# Connector.net
KiCad netlist of a schematic drawn in Altium Designer
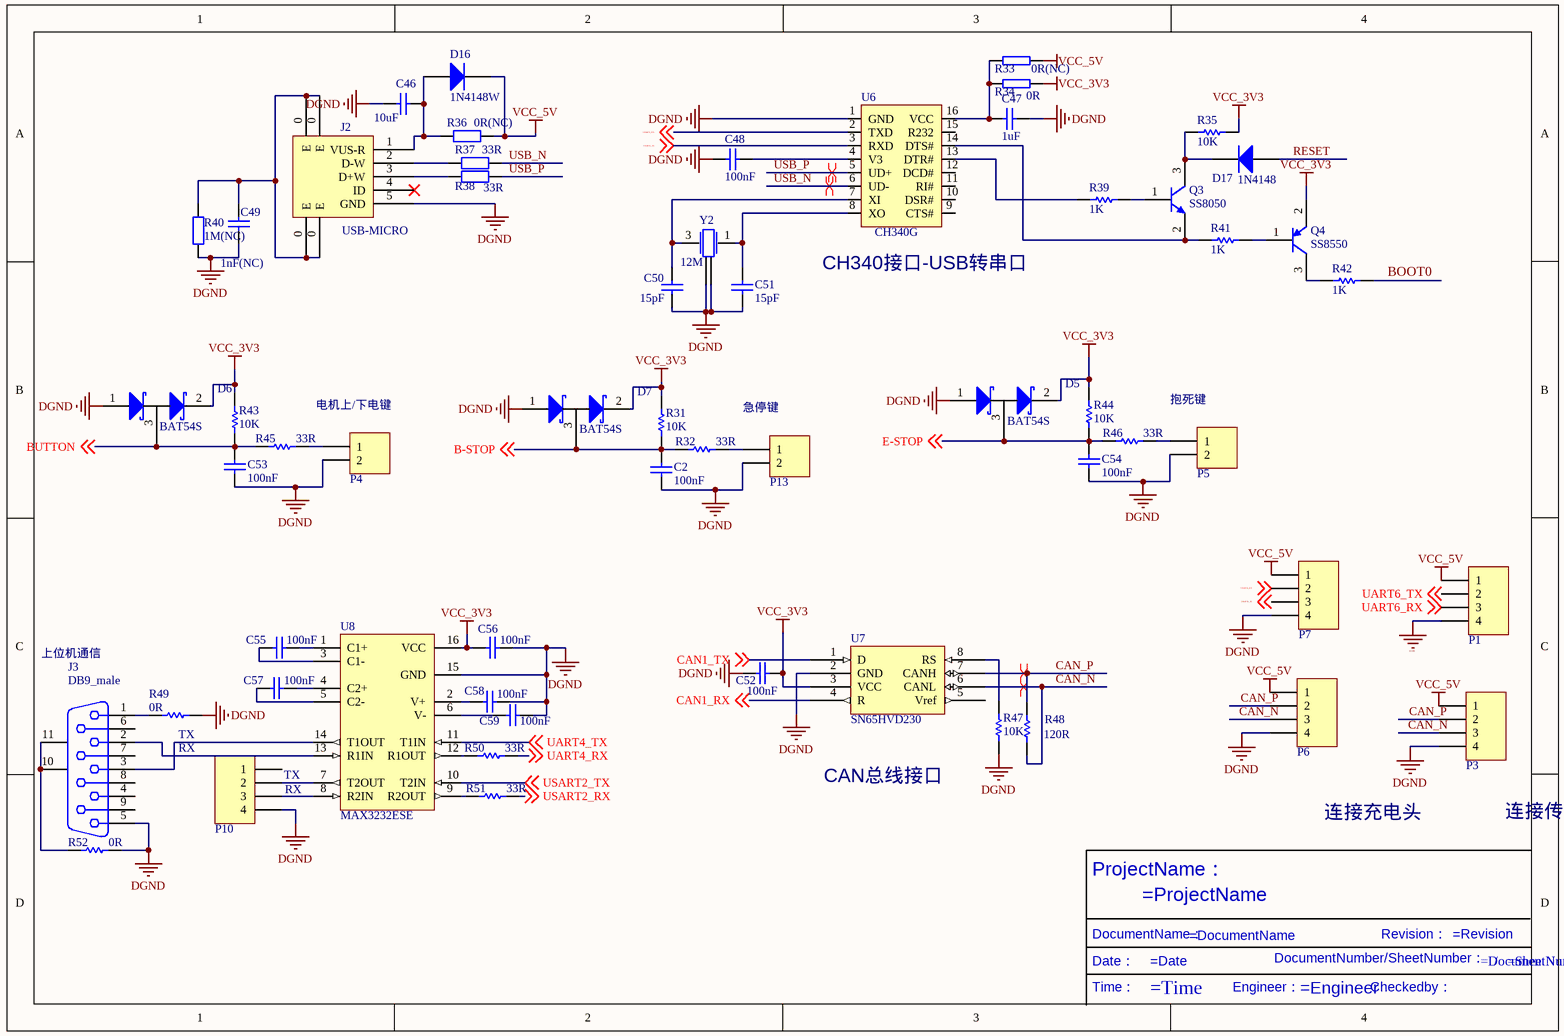
[diagram p0: Connector.SchDoc]

(export (version "E")
  (design (tool "Eeschema 10.0.6"))
  (components
    (comp (ref "C2")
      (value "100nF")
      (footprint "C-RAD-0805")
      (description "Capacitor")
      (fields (field (name "Comment") "100nF/±10%/50Vdc") (field (name "PUBLISHER") "Altium Limited"))
      (libsource (lib "boocax_schlib") (part "Cap"))
    )
    (comp (ref "C46")
      (value "10uF")
      (footprint "C-RAD-0805")
      (description "Capacitor")
      (fields (field (name "Comment") "10uF/±10%/50Vdc") (field (name "PUBLISHER") "Altium Limited"))
      (libsource (lib "boocax_schlib") (part "Cap"))
    )
    (comp (ref "C47")
      (value "1uF")
      (footprint "C-RAD-0805")
      (description "Capacitor")
      (fields (field (name "Comment") "1uF/±10%/50Vdc") (field (name "PUBLISHER") "Altium Limited"))
      (libsource (lib "boocax_schlib") (part "Cap"))
    )
    (comp (ref "C48")
      (value "100nF")
      (footprint "C-RAD-0805")
      (description "Capacitor")
      (fields (field (name "Comment") "100nF/±10%/50Vdc") (field (name "PUBLISHER") "Altium Limited"))
      (libsource (lib "boocax_schlib") (part "Cap"))
    )
    (comp (ref "C49")
      (value "1nF(NC)")
      (footprint "C-RAD-0805")
      (description "Capacitor")
      (fields (field (name "Comment") "Cap") (field (name "PUBLISHER") "Altium Limited"))
      (libsource (lib "boocax_schlib") (part "Cap"))
    )
    (comp (ref "C50")
      (value "15pF")
      (footprint "C-RAD-0805")
      (description "Capacitor")
      (fields (field (name "Comment") "15pF/±10%/50Vdc") (field (name "PUBLISHER") "Altium Limited"))
      (libsource (lib "boocax_schlib") (part "Cap"))
    )
    (comp (ref "C51")
      (value "15pF")
      (footprint "C-RAD-0805")
      (description "Capacitor")
      (fields (field (name "Comment") "15pF/±10%/50Vdc") (field (name "PUBLISHER") "Altium Limited"))
      (libsource (lib "boocax_schlib") (part "Cap"))
    )
    (comp (ref "C52")
      (value "100nF")
      (footprint "C-RAD-0805")
      (description "Capacitor")
      (fields (field (name "Comment") "100nF/±10%/50Vdc") (field (name "PUBLISHER") "Altium Limited"))
      (libsource (lib "boocax_schlib") (part "Cap"))
    )
    (comp (ref "C53")
      (value "100nF")
      (footprint "C-RAD-0805")
      (description "Capacitor")
      (fields (field (name "Comment") "100nF/±10%/50Vdc") (field (name "PUBLISHER") "Altium Limited"))
      (libsource (lib "boocax_schlib") (part "Cap"))
    )
    (comp (ref "C54")
      (value "100nF")
      (footprint "C-RAD-0805")
      (description "Capacitor")
      (fields (field (name "Comment") "100nF/±10%/50Vdc") (field (name "PUBLISHER") "Altium Limited"))
      (libsource (lib "boocax_schlib") (part "Cap"))
    )
    (comp (ref "C55")
      (value "100nF")
      (footprint "C-RAD-0805")
      (description "Capacitor")
      (fields (field (name "Comment") "100nF/±10%/50Vdc") (field (name "PUBLISHER") "Altium Limited"))
      (libsource (lib "boocax_schlib") (part "Cap"))
    )
    (comp (ref "C56")
      (value "100nF")
      (footprint "C-RAD-0805")
      (description "Capacitor")
      (fields (field (name "Comment") "100nF/±10%/50Vdc") (field (name "PUBLISHER") "Altium Limited"))
      (libsource (lib "boocax_schlib") (part "Cap"))
    )
    (comp (ref "C57")
      (value "100nF")
      (footprint "C-RAD-0805")
      (description "Capacitor")
      (fields (field (name "Comment") "100nF/±10%/50Vdc") (field (name "PUBLISHER") "Altium Limited"))
      (libsource (lib "boocax_schlib") (part "Cap"))
    )
    (comp (ref "C58")
      (value "100nF")
      (footprint "C-RAD-0805")
      (description "Capacitor")
      (fields (field (name "Comment") "100nF/±10%/50Vdc") (field (name "PUBLISHER") "Altium Limited"))
      (libsource (lib "boocax_schlib") (part "Cap"))
    )
    (comp (ref "C59")
      (value "100nF")
      (footprint "C-RAD-0805")
      (description "Capacitor")
      (fields (field (name "Comment") "100nF/±10%/50Vdc") (field (name "PUBLISHER") "Altium Limited"))
      (libsource (lib "boocax_schlib") (part "Cap"))
    )
    (comp (ref "D5")
      (value "BAT54S")
      (footprint "SOT-23")
      (description "双向肖特基二极管")
      (libsource (lib "Schlib1") (part "BAT54S"))
    )
    (comp (ref "D6")
      (value "BAT54S")
      (footprint "SOT-23")
      (description "双向肖特基二极管")
      (libsource (lib "Schlib1") (part "BAT54S"))
    )
    (comp (ref "D7")
      (value "BAT54S")
      (footprint "SOT-23")
      (description "双向肖特基二极管")
      (libsource (lib "Schlib1") (part "BAT54S"))
    )
    (comp (ref "D16")
      (value "1N4148W")
      (footprint "DIODE-1206")
      (description "二极管")
      (fields (field (name "PUBLISHER") "Altium Limited"))
      (libsource (lib "Sensor_V1.0.0") (part "Diode"))
    )
    (comp (ref "D17")
      (value "1N4148")
      (footprint "DIODE-1206")
      (description "二极管")
      (fields (field (name "Comment") "1N4148W") (field (name "PUBLISHER") "Altium Limited"))
      (libsource (lib "Sensor_V1.0.0") (part "Diode"))
    )
    (comp (ref "J2")
      (value "USB-MICRO")
      (footprint "USB-MICRO-1")
      (libsource (lib "boocax_schlib") (part "USB-MICRO"))
    )
    (comp (ref "J3")
      (value "DB9_male")
      (footprint "DB9-M")
      (description "串口")
      (fields (field (name "PUBLISHER") "Altium Limited"))
      (libsource (lib "founder") (part "D Connector 9"))
    )
    (comp (ref "P1")
      (value "Header 4")
      (footprint "SM04B-PBV")
      (description "接插件")
      (fields (field (name "PUBLISHER") "Altium Limited"))
      (libsource (lib "fszhang") (part "Header 4"))
    )
    (comp (ref "P3")
      (value "Header 4")
      (footprint "SM04B-PBV")
      (description "接插件")
      (fields (field (name "PUBLISHER") "Altium Limited"))
      (libsource (lib "fszhang") (part "Header 4"))
    )
    (comp (ref "P4")
      (value "Header 2")
      (footprint "MOLEX-2P")
      (description "接插件")
      (fields (field (name "PUBLISHER") "Altium Limited"))
      (libsource (lib "Fszhang") (part "Header 2"))
    )
    (comp (ref "P5")
      (value "Header 2")
      (footprint "MOLEX-2P")
      (description "接插件")
      (fields (field (name "PUBLISHER") "Altium Limited"))
      (libsource (lib "Fszhang") (part "Header 2"))
    )
    (comp (ref "P6")
      (value "Header 4")
      (footprint "SM04B-PBV")
      (description "接插件")
      (fields (field (name "PUBLISHER") "Altium Limited"))
      (libsource (lib "fszhang") (part "Header 4"))
    )
    (comp (ref "P7")
      (value "Header 4")
      (footprint "SM04B-PBV")
      (description "接插件")
      (fields (field (name "PUBLISHER") "Altium Limited"))
      (libsource (lib "fszhang") (part "Header 4"))
    )
    (comp (ref "P10")
      (value "Header 4")
      (footprint "SM04B-PBV")
      (description "接插件")
      (fields (field (name "PUBLISHER") "Altium Limited"))
      (libsource (lib "") (part "Header 4_1"))
    )
    (comp (ref "P13")
      (value "Header 2")
      (footprint "MOLEX-2P")
      (description "接插件")
      (fields (field (name "PUBLISHER") "Altium Limited"))
      (libsource (lib "Fszhang") (part "Header 2"))
    )
    (comp (ref "Q3")
      (value "SS8050")
      (footprint "SOT-23")
      (description "NPN贴片三极管")
      (fields (field (name "PUBLISHER") "Altium Limited"))
      (libsource (lib "Fszhang") (part "SS8050"))
    )
    (comp (ref "Q4")
      (value "SS8550")
      (footprint "SOT-23")
      (description "PNP贴片三极管")
      (fields (field (name "PUBLISHER") "Altium Limited"))
      (libsource (lib "Fszhang") (part "SS8550"))
    )
    (comp (ref "R31")
      (value "10K")
      (footprint "0805-1")
      (description "Resistor")
      (fields (field (name "Comment") "10K 5% 1/16W 0805") (field (name "PUBLISHER") "Altium Limited"))
      (libsource (lib "boocax_schlib") (part "Res1"))
    )
    (comp (ref "R32")
      (value "33R")
      (footprint "0805-1")
      (description "Resistor")
      (fields (field (name "Comment") "33R 5% 1/16W 0805") (field (name "PUBLISHER") "Altium Limited"))
      (libsource (lib "boocax_schlib") (part "Res1"))
    )
    (comp (ref "R33")
      (value "0R(NC)")
      (footprint "0805-1")
      (fields (field (name "Comment") "0R 5% 1/16W 0805(NC)"))
      (libsource (lib "luyjsch") (part "RES"))
    )
    (comp (ref "R34")
      (value "0R")
      (footprint "0805-1")
      (fields (field (name "Comment") "0R 5% 1/16W 0805"))
      (libsource (lib "luyjsch") (part "RES"))
    )
    (comp (ref "R35")
      (value "10K")
      (footprint "0805-1")
      (description "Resistor")
      (fields (field (name "Comment") "10K 5% 1/16W 0805") (field (name "PUBLISHER") "Altium Limited"))
      (libsource (lib "boocax_schlib") (part "Res1"))
    )
    (comp (ref "R36")
      (value "0R(NC)")
      (footprint "0805-1")
      (description "贴片电阻")
      (fields (field (name "Comment") "0R 5% 1/16W 0805(NC)") (field (name "PUBLISHER") "Altium Limited"))
      (libsource (lib "Compiled_Libraries") (part "Res1"))
    )
    (comp (ref "R37")
      (value "33R")
      (footprint "0805-1")
      (description "贴片电阻")
      (fields (field (name "Comment") "33R 5% 1/16W 0805") (field (name "PUBLISHER") "Altium Limited"))
      (libsource (lib "Compiled_Libraries") (part "Res1"))
    )
    (comp (ref "R38")
      (value "33R")
      (footprint "0805-1")
      (description "贴片电阻")
      (fields (field (name "Comment") "33R 5% 1/16W 0805") (field (name "PUBLISHER") "Altium Limited"))
      (libsource (lib "Compiled_Libraries") (part "Res1"))
    )
    (comp (ref "R39")
      (value "1K")
      (footprint "0805-1")
      (description "Resistor")
      (fields (field (name "Comment") "1K 5% 1/16W 0805") (field (name "PUBLISHER") "Altium Limited"))
      (libsource (lib "boocax_schlib") (part "Res1"))
    )
    (comp (ref "R40")
      (value "1M(NC)")
      (footprint "0805-1")
      (description "贴片电阻")
      (fields (field (name "Comment") "1M 5% 1/16W 0805(NC)") (field (name "PUBLISHER") "Altium Limited"))
      (libsource (lib "") (part "Res1_1"))
    )
    (comp (ref "R41")
      (value "1K")
      (footprint "0805-1")
      (description "Resistor")
      (fields (field (name "Comment") "1K 5% 1/16W 0805") (field (name "PUBLISHER") "Altium Limited"))
      (libsource (lib "boocax_schlib") (part "Res1"))
    )
    (comp (ref "R42")
      (value "1K")
      (footprint "0805-1")
      (description "Resistor")
      (fields (field (name "Comment") "1K 5% 1/16W 0805") (field (name "PUBLISHER") "Altium Limited"))
      (libsource (lib "boocax_schlib") (part "Res1"))
    )
    (comp (ref "R43")
      (value "10K")
      (footprint "0805-1")
      (description "Resistor")
      (fields (field (name "Comment") "10K 5% 1/16W 0805") (field (name "PUBLISHER") "Altium Limited"))
      (libsource (lib "boocax_schlib") (part "Res1"))
    )
    (comp (ref "R44")
      (value "10K")
      (footprint "0805-1")
      (description "Resistor")
      (fields (field (name "Comment") "10K 5% 1/16W 0805") (field (name "PUBLISHER") "Altium Limited"))
      (libsource (lib "boocax_schlib") (part "Res1"))
    )
    (comp (ref "R45")
      (value "33R")
      (footprint "0805-1")
      (description "Resistor")
      (fields (field (name "Comment") "33R 5% 1/16W 0805") (field (name "PUBLISHER") "Altium Limited"))
      (libsource (lib "boocax_schlib") (part "Res1"))
    )
    (comp (ref "R46")
      (value "33R")
      (footprint "0805-1")
      (description "Resistor")
      (fields (field (name "Comment") "33R 5% 1/16W 0805") (field (name "PUBLISHER") "Altium Limited"))
      (libsource (lib "boocax_schlib") (part "Res1"))
    )
    (comp (ref "R47")
      (value "10K")
      (footprint "0805-1")
      (description "Resistor")
      (fields (field (name "Comment") "10K 5% 1/16W 0805") (field (name "PUBLISHER") "Altium Limited"))
      (libsource (lib "boocax_schlib") (part "Res1"))
    )
    (comp (ref "R48")
      (value "120R")
      (footprint "0805-1")
      (description "Resistor")
      (fields (field (name "Comment") "120R 5% 1/16W 0805") (field (name "PUBLISHER") "Altium Limited"))
      (libsource (lib "boocax_schlib") (part "Res1"))
    )
    (comp (ref "R49")
      (value "0R")
      (footprint "0805-1")
      (description "Resistor")
      (fields (field (name "Comment") "0R 5% 1/16W 0805") (field (name "PUBLISHER") "Altium Limited"))
      (libsource (lib "boocax_schlib") (part "Res1"))
    )
    (comp (ref "R50")
      (value "33R")
      (footprint "0805-1")
      (description "Resistor")
      (fields (field (name "Comment") "33R 5% 1/16W 0805") (field (name "PUBLISHER") "Altium Limited"))
      (libsource (lib "boocax_schlib") (part "Res1"))
    )
    (comp (ref "R51")
      (value "33R")
      (footprint "0805-1")
      (description "Resistor")
      (fields (field (name "Comment") "33R 5% 1/16W 0805") (field (name "PUBLISHER") "Altium Limited"))
      (libsource (lib "boocax_schlib") (part "Res1"))
    )
    (comp (ref "R52")
      (value "0R")
      (footprint "0805-1")
      (description "Resistor")
      (fields (field (name "Comment") "0R 5% 1/16W 0805") (field (name "PUBLISHER") "Altium Limited"))
      (libsource (lib "boocax_schlib") (part "Res1"))
    )
    (comp (ref "U6")
      (value "CH340G")
      (footprint "SOP16")
      (description "串口转USB芯片")
      (libsource (lib "luyjsch") (part "CH340G"))
    )
    (comp (ref "U7")
      (value "SN65HVD230")
      (footprint "SO8-SN65HVD230")
      (libsource (lib "boocax_schlib") (part "SN65HVD230D"))
    )
    (comp (ref "U8")
      (value "MAX3232ESE")
      (footprint "SOP16")
      (description "+5V Powered, Multi-Channel RS-232 Driver/Receiver")
      (fields (field (name "PUBLISHER") "Altium Limited"))
      (libsource (lib "BABA03A-V1") (part "MAX3232ESE"))
    )
    (comp (ref "Y2")
      (value "12M")
      (footprint "EPSON-16M")
      (description "晶振")
      (fields (field (name "Comment") "XTAL-12M"))
      (libsource (lib "fszhang") (part "XTAL-4PIN"))
    )
  )
  (nets
    (net (code "9") (name "/BOOT0") (class "Default")
      (node (ref "R42") (pin "2") (pinfunction "2_2") (pintype "passive"))
    )
    (net (code "10") (name "/CAN_N") (class "Default")
      (node (ref "P3") (pin "3") (pinfunction "3_3") (pintype "passive"))
      (node (ref "P6") (pin "3") (pinfunction "3_3") (pintype "passive"))
      (node (ref "R48") (pin "2") (pinfunction "2_2") (pintype "passive"))
      (node (ref "U7") (pin "6") (pinfunction "CANL_6") (pintype "bidirectional"))
    )
    (net (code "11") (name "/CAN_P") (class "Default")
      (node (ref "P3") (pin "2") (pinfunction "2_2") (pintype "passive"))
      (node (ref "P6") (pin "2") (pinfunction "2_2") (pintype "passive"))
      (node (ref "R48") (pin "1") (pinfunction "1_1") (pintype "passive"))
      (node (ref "U7") (pin "7") (pinfunction "CANH_7") (pintype "bidirectional"))
    )
    (net (code "18") (name "/RESET") (class "Default")
      (node (ref "D17") (pin "1") (pinfunction "A_1") (pintype "passive"))
    )
    (net (code "21") (name "/USB_N") (class "Default")
      (node (ref "R37") (pin "2") (pinfunction "2_2") (pintype "passive"))
      (node (ref "U6") (pin "6") (pinfunction "UD-_6") (pintype "passive"))
    )
    (net (code "22") (name "/USB_P") (class "Default")
      (node (ref "R38") (pin "2") (pinfunction "2_2") (pintype "passive"))
      (node (ref "U6") (pin "5") (pinfunction "UD+_5") (pintype "passive"))
    )
    (net (code "24") (name "B-STOP") (class "Default")
      (node (ref "C2") (pin "1") (pinfunction "1_1") (pintype "passive"))
      (node (ref "D7") (pin "3") (pinfunction "AK_3") (pintype "passive"))
      (node (ref "R31") (pin "1") (pinfunction "1_1") (pintype "passive"))
      (node (ref "R32") (pin "2") (pinfunction "2_2") (pintype "passive"))
    )
    (net (code "25") (name "BUTTON") (class "Default")
      (node (ref "C53") (pin "1") (pinfunction "1_1") (pintype "passive"))
      (node (ref "D6") (pin "3") (pinfunction "AK_3") (pintype "passive"))
      (node (ref "R43") (pin "1") (pinfunction "1_1") (pintype "passive"))
      (node (ref "R45") (pin "2") (pinfunction "2_2") (pintype "passive"))
    )
    (net (code "26") (name "CAN1_RX") (class "Default")
      (node (ref "U7") (pin "4") (pinfunction "R_4") (pintype "output"))
    )
    (net (code "27") (name "CAN1_TX") (class "Default")
      (node (ref "U7") (pin "1") (pinfunction "D_1") (pintype "input"))
    )
    (net (code "28") (name "DGND") (class "Default")
      (node (ref "C2") (pin "2") (pinfunction "2_2") (pintype "passive"))
      (node (ref "C46") (pin "2") (pinfunction "2_2") (pintype "passive"))
      (node (ref "C47") (pin "2") (pinfunction "2_2") (pintype "passive"))
      (node (ref "C48") (pin "2") (pinfunction "2_2") (pintype "passive"))
      (node (ref "C49") (pin "2") (pinfunction "2_2") (pintype "passive"))
      (node (ref "C50") (pin "2") (pinfunction "2_2") (pintype "passive"))
      (node (ref "C51") (pin "2") (pinfunction "2_2") (pintype "passive"))
      (node (ref "C52") (pin "1") (pinfunction "1_1") (pintype "passive"))
      (node (ref "C53") (pin "2") (pinfunction "2_2") (pintype "passive"))
      (node (ref "C54") (pin "2") (pinfunction "2_2") (pintype "passive"))
      (node (ref "C56") (pin "1") (pinfunction "1_1") (pintype "passive"))
      (node (ref "C58") (pin "1") (pinfunction "1_1") (pintype "passive"))
      (node (ref "C59") (pin "1") (pinfunction "1_1") (pintype "passive"))
      (node (ref "D5") (pin "1") (pinfunction "A_1") (pintype "passive"))
      (node (ref "D6") (pin "1") (pinfunction "A_1") (pintype "passive"))
      (node (ref "D7") (pin "1") (pinfunction "A_1") (pintype "passive"))
      (node (ref "J2") (pin "5") (pinfunction "GND_5") (pintype "passive"))
      (node (ref "J3") (pin "5") (pinfunction "5_5") (pintype "passive"))
      (node (ref "P1") (pin "4") (pinfunction "4_4") (pintype "passive"))
      (node (ref "P10") (pin "4") (pinfunction "4_4") (pintype "passive"))
      (node (ref "P13") (pin "2") (pinfunction "2_2") (pintype "passive"))
      (node (ref "P3") (pin "4") (pinfunction "4_4") (pintype "passive"))
      (node (ref "P4") (pin "2") (pinfunction "2_2") (pintype "passive"))
      (node (ref "P5") (pin "2") (pinfunction "2_2") (pintype "passive"))
      (node (ref "P6") (pin "4") (pinfunction "4_4") (pintype "passive"))
      (node (ref "P7") (pin "4") (pinfunction "4_4") (pintype "passive"))
      (node (ref "R40") (pin "1") (pinfunction "1_1") (pintype "passive"))
      (node (ref "R47") (pin "2") (pinfunction "2_2") (pintype "passive"))
      (node (ref "R49") (pin "1") (pinfunction "1_1") (pintype "passive"))
      (node (ref "R52") (pin "1") (pinfunction "1_1") (pintype "passive"))
      (node (ref "U6") (pin "1") (pinfunction "GND_1") (pintype "passive"))
      (node (ref "U7") (pin "2") (pinfunction "GND_2") (pintype "power_in"))
      (node (ref "U8") (pin "15") (pinfunction "GND_15") (pintype "power_in"))
      (node (ref "Y2") (pin "2") (pinfunction "2_2") (pintype "passive"))
      (node (ref "Y2") (pin "4") (pinfunction "4_4") (pintype "passive"))
    )
    (net (code "29") (name "E-STOP") (class "Default")
      (node (ref "C54") (pin "1") (pinfunction "1_1") (pintype "passive"))
      (node (ref "D5") (pin "3") (pinfunction "AK_3") (pintype "passive"))
      (node (ref "R44") (pin "1") (pinfunction "1_1") (pintype "passive"))
      (node (ref "R46") (pin "2") (pinfunction "2_2") (pintype "passive"))
    )
    (net (code "30") (name "Net-(D16-A)") (class "Default")
      (node (ref "C46") (pin "1") (pinfunction "1_1") (pintype "passive"))
      (node (ref "D16") (pin "1") (pinfunction "A_1") (pintype "passive"))
      (node (ref "J2") (pin "1") (pinfunction "VUS-R_1") (pintype "passive"))
      (node (ref "R36") (pin "1") (pinfunction "1_1") (pintype "passive"))
    )
    (net (code "31") (name "Net-(D17-K)") (class "Default")
      (node (ref "D17") (pin "2") (pinfunction "K_2") (pintype "passive"))
      (node (ref "Q3") (pin "3") (pinfunction "C_3") (pintype "passive"))
      (node (ref "R35") (pin "2") (pinfunction "2_2") (pintype "passive"))
    )
    (net (code "32") (name "Net-(J2-D+W)") (class "Default")
      (node (ref "J2") (pin "3") (pinfunction "D+W_3") (pintype "passive"))
      (node (ref "R38") (pin "1") (pinfunction "1_1") (pintype "passive"))
    )
    (net (code "33") (name "Net-(J2-D-W)") (class "Default")
      (node (ref "J2") (pin "2") (pinfunction "D-W_2") (pintype "passive"))
      (node (ref "R37") (pin "1") (pinfunction "1_1") (pintype "passive"))
    )
    (net (code "34") (name "Net-(J2-E)") (class "Default")
      (node (ref "C49") (pin "1") (pinfunction "1_1") (pintype "passive"))
      (node (ref "J2") (pin "0") (pinfunction "E_0") (pintype "passive"))
      (node (ref "R40") (pin "2") (pinfunction "2_2") (pintype "passive"))
    )
    (net (code "35") (name "Net-(J3-MH1)") (class "Default")
      (node (ref "J3") (pin "10") (pinfunction "MH1_10") (pintype "passive"))
      (node (ref "J3") (pin "11") (pinfunction "MH2_11") (pintype "passive"))
      (node (ref "R52") (pin "2") (pinfunction "2_2") (pintype "passive"))
    )
    (net (code "36") (name "Net-(J3-Pad1)") (class "Default")
      (node (ref "J3") (pin "1") (pinfunction "1_1") (pintype "passive"))
      (node (ref "R49") (pin "2") (pinfunction "2_2") (pintype "passive"))
    )
    (net (code "37") (name "Net-(P4-Pad1)") (class "Default")
      (node (ref "P4") (pin "1") (pinfunction "1_1") (pintype "passive"))
      (node (ref "R45") (pin "1") (pinfunction "1_1") (pintype "passive"))
    )
    (net (code "38") (name "Net-(P5-Pad1)") (class "Default")
      (node (ref "P5") (pin "1") (pinfunction "1_1") (pintype "passive"))
      (node (ref "R46") (pin "1") (pinfunction "1_1") (pintype "passive"))
    )
    (net (code "39") (name "Net-(P13-Pad1)") (class "Default")
      (node (ref "P13") (pin "1") (pinfunction "1_1") (pintype "passive"))
      (node (ref "R32") (pin "1") (pinfunction "1_1") (pintype "passive"))
    )
    (net (code "40") (name "Net-(Q3-B)") (class "Default")
      (node (ref "Q3") (pin "1") (pinfunction "B_1") (pintype "passive"))
      (node (ref "R39") (pin "1") (pinfunction "1_1") (pintype "passive"))
    )
    (net (code "41") (name "Net-(Q3-E)") (class "Default")
      (node (ref "Q3") (pin "2") (pinfunction "E_2") (pintype "passive"))
      (node (ref "R41") (pin "2") (pinfunction "2_2") (pintype "passive"))
      (node (ref "U6") (pin "14") (pinfunction "DTS#_14") (pintype "passive"))
    )
    (net (code "42") (name "Net-(Q4-B)") (class "Default")
      (node (ref "Q4") (pin "1") (pinfunction "B_1") (pintype "passive"))
      (node (ref "R41") (pin "1") (pinfunction "1_1") (pintype "passive"))
    )
    (net (code "43") (name "Net-(Q4-C)") (class "Default")
      (node (ref "Q4") (pin "3") (pinfunction "C_3") (pintype "passive"))
      (node (ref "R42") (pin "1") (pinfunction "1_1") (pintype "passive"))
    )
    (net (code "44") (name "Net-(U6-DTR#)") (class "Default")
      (node (ref "R39") (pin "2") (pinfunction "2_2") (pintype "passive"))
      (node (ref "U6") (pin "13") (pinfunction "DTR#_13") (pintype "passive"))
    )
    (net (code "45") (name "Net-(U6-V3)") (class "Default")
      (node (ref "C48") (pin "1") (pinfunction "1_1") (pintype "passive"))
      (node (ref "U6") (pin "4") (pinfunction "V3_4") (pintype "passive"))
    )
    (net (code "46") (name "Net-(U6-VCC)") (class "Default")
      (node (ref "C47") (pin "1") (pinfunction "1_1") (pintype "passive"))
      (node (ref "R33") (pin "2") (pinfunction "2_2") (pintype "passive"))
      (node (ref "R34") (pin "2") (pinfunction "2_2") (pintype "passive"))
      (node (ref "U6") (pin "16") (pinfunction "VCC_16") (pintype "passive"))
    )
    (net (code "47") (name "Net-(U6-XI)") (class "Default")
      (node (ref "C50") (pin "1") (pinfunction "1_1") (pintype "passive"))
      (node (ref "U6") (pin "7") (pinfunction "XI_7") (pintype "passive"))
      (node (ref "Y2") (pin "3") (pinfunction "3_3") (pintype "passive"))
    )
    (net (code "48") (name "Net-(U6-XO)") (class "Default")
      (node (ref "C51") (pin "1") (pinfunction "1_1") (pintype "passive"))
      (node (ref "U6") (pin "8") (pinfunction "XO_8") (pintype "passive"))
      (node (ref "Y2") (pin "1") (pinfunction "1_1") (pintype "passive"))
    )
    (net (code "49") (name "Net-(U7-RS)") (class "Default")
      (node (ref "R47") (pin "1") (pinfunction "1_1") (pintype "passive"))
      (node (ref "U7") (pin "8") (pinfunction "RS_8") (pintype "input"))
    )
    (net (code "50") (name "Net-(U8-C1+)") (class "Default")
      (node (ref "C55") (pin "1") (pinfunction "1_1") (pintype "passive"))
      (node (ref "U8") (pin "1") (pinfunction "C1+_1") (pintype "passive"))
    )
    (net (code "51") (name "Net-(U8-C1-)") (class "Default")
      (node (ref "C55") (pin "2") (pinfunction "2_2") (pintype "passive"))
      (node (ref "U8") (pin "3") (pinfunction "C1-_3") (pintype "passive"))
    )
    (net (code "52") (name "Net-(U8-C2+)") (class "Default")
      (node (ref "C57") (pin "1") (pinfunction "1_1") (pintype "passive"))
      (node (ref "U8") (pin "4") (pinfunction "C2+_4") (pintype "passive"))
    )
    (net (code "53") (name "Net-(U8-C2-)") (class "Default")
      (node (ref "C57") (pin "2") (pinfunction "2_2") (pintype "passive"))
      (node (ref "U8") (pin "5") (pinfunction "C2-_5") (pintype "passive"))
    )
    (net (code "54") (name "Net-(U8-R1IN)") (class "Default")
      (node (ref "J3") (pin "2") (pinfunction "2_2") (pintype "passive"))
      (node (ref "U8") (pin "13") (pinfunction "R1IN_13") (pintype "input"))
    )
    (net (code "55") (name "Net-(U8-R1OUT)") (class "Default")
      (node (ref "R50") (pin "1") (pinfunction "1_1") (pintype "passive"))
      (node (ref "U8") (pin "12") (pinfunction "R1OUT_12") (pintype "output"))
    )
    (net (code "56") (name "Net-(U8-R2IN)") (class "Default")
      (node (ref "P10") (pin "3") (pinfunction "3_3") (pintype "passive"))
      (node (ref "U8") (pin "8") (pinfunction "R2IN_8") (pintype "input"))
    )
    (net (code "57") (name "Net-(U8-R2OUT)") (class "Default")
      (node (ref "R51") (pin "1") (pinfunction "1_1") (pintype "passive"))
      (node (ref "U8") (pin "9") (pinfunction "R2OUT_9") (pintype "output"))
    )
    (net (code "58") (name "Net-(U8-T1OUT)") (class "Default")
      (node (ref "J3") (pin "3") (pinfunction "3_3") (pintype "passive"))
      (node (ref "U8") (pin "14") (pinfunction "T1OUT_14") (pintype "output"))
    )
    (net (code "59") (name "Net-(U8-T2OUT)") (class "Default")
      (node (ref "P10") (pin "2") (pinfunction "2_2") (pintype "passive"))
      (node (ref "U8") (pin "7") (pinfunction "T2OUT_7") (pintype "output"))
    )
    (net (code "60") (name "Net-(U8-V+)") (class "Default")
      (node (ref "C58") (pin "2") (pinfunction "2_2") (pintype "passive"))
      (node (ref "U8") (pin "2") (pinfunction "V+_2") (pintype "power_in"))
    )
    (net (code "61") (name "Net-(U8-V-)") (class "Default")
      (node (ref "C59") (pin "2") (pinfunction "2_2") (pintype "passive"))
      (node (ref "U8") (pin "6") (pinfunction "V-_6") (pintype "power_in"))
    )
    (net (code "62") (name "UART4_RX") (class "Default")
      (node (ref "R50") (pin "2") (pinfunction "2_2") (pintype "passive"))
    )
    (net (code "63") (name "UART4_TX") (class "Default")
      (node (ref "U8") (pin "11") (pinfunction "T1IN_11") (pintype "input"))
    )
    (net (code "64") (name "UART6_RX") (class "Default")
      (node (ref "P1") (pin "3") (pinfunction "3_3") (pintype "passive"))
    )
    (net (code "65") (name "UART6_TX") (class "Default")
      (node (ref "P1") (pin "2") (pinfunction "2_2") (pintype "passive"))
    )
    (net (code "66") (name "USART1_RX") (class "Default")
      (node (ref "U6") (pin "2") (pinfunction "TXD_2") (pintype "passive"))
    )
    (net (code "67") (name "USART1_TX") (class "Default")
      (node (ref "U6") (pin "3") (pinfunction "RXD_3") (pintype "passive"))
    )
    (net (code "68") (name "USART2_RX") (class "Default")
      (node (ref "R51") (pin "2") (pinfunction "2_2") (pintype "passive"))
    )
    (net (code "69") (name "USART2_TX") (class "Default")
      (node (ref "U8") (pin "10") (pinfunction "T2IN_10") (pintype "input"))
    )
    (net (code "70") (name "USART3_RX") (class "Default")
      (node (ref "P7") (pin "2") (pinfunction "2_2") (pintype "passive"))
    )
    (net (code "71") (name "USART3_TX") (class "Default")
      (node (ref "P7") (pin "3") (pinfunction "3_3") (pintype "passive"))
    )
    (net (code "72") (name "VCC_3V3") (class "Default")
      (node (ref "C52") (pin "2") (pinfunction "2_2") (pintype "passive"))
      (node (ref "C56") (pin "2") (pinfunction "2_2") (pintype "passive"))
      (node (ref "D5") (pin "2") (pinfunction "K_2") (pintype "passive"))
      (node (ref "D6") (pin "2") (pinfunction "K_2") (pintype "passive"))
      (node (ref "D7") (pin "2") (pinfunction "K_2") (pintype "passive"))
      (node (ref "Q4") (pin "2") (pinfunction "E_2") (pintype "passive"))
      (node (ref "R31") (pin "2") (pinfunction "2_2") (pintype "passive"))
      (node (ref "R34") (pin "1") (pinfunction "1_1") (pintype "passive"))
      (node (ref "R35") (pin "1") (pinfunction "1_1") (pintype "passive"))
      (node (ref "R43") (pin "2") (pinfunction "2_2") (pintype "passive"))
      (node (ref "R44") (pin "2") (pinfunction "2_2") (pintype "passive"))
      (node (ref "U7") (pin "3") (pinfunction "VCC_3") (pintype "power_in"))
      (node (ref "U8") (pin "16") (pinfunction "VCC_16") (pintype "power_in"))
    )
    (net (code "73") (name "VCC_5V") (class "Default")
      (node (ref "D16") (pin "2") (pinfunction "K_2") (pintype "passive"))
      (node (ref "P1") (pin "1") (pinfunction "1_1") (pintype "passive"))
      (node (ref "P3") (pin "1") (pinfunction "1_1") (pintype "passive"))
      (node (ref "P6") (pin "1") (pinfunction "1_1") (pintype "passive"))
      (node (ref "P7") (pin "1") (pinfunction "1_1") (pintype "passive"))
      (node (ref "R33") (pin "1") (pinfunction "1_1") (pintype "passive"))
      (node (ref "R36") (pin "2") (pinfunction "2_2") (pintype "passive"))
    )
    (net (code "74") (name "unconnected-(J2-ID-Pad4)") (class "Default")
      (node (ref "J2") (pin "4") (pinfunction "ID_4") (pintype "passive+no_connect"))
    )
    (net (code "75") (name "unconnected-(J3-Pad4)") (class "Default")
      (node (ref "J3") (pin "4") (pinfunction "4_4") (pintype "passive"))
    )
    (net (code "76") (name "unconnected-(J3-Pad6)") (class "Default")
      (node (ref "J3") (pin "6") (pinfunction "6_6") (pintype "passive"))
    )
    (net (code "77") (name "unconnected-(J3-Pad7)") (class "Default")
      (node (ref "J3") (pin "7") (pinfunction "7_7") (pintype "passive"))
    )
    (net (code "78") (name "unconnected-(J3-Pad8)") (class "Default")
      (node (ref "J3") (pin "8") (pinfunction "8_8") (pintype "passive"))
    )
    (net (code "79") (name "unconnected-(J3-Pad9)") (class "Default")
      (node (ref "J3") (pin "9") (pinfunction "9_9") (pintype "passive"))
    )
    (net (code "80") (name "unconnected-(P10-Pad1)") (class "Default")
      (node (ref "P10") (pin "1") (pinfunction "1_1") (pintype "passive"))
    )
    (net (code "81") (name "unconnected-(U6-CTS#-Pad9)") (class "Default")
      (node (ref "U6") (pin "9") (pinfunction "CTS#_9") (pintype "passive"))
    )
    (net (code "82") (name "unconnected-(U6-DCD#-Pad12)") (class "Default")
      (node (ref "U6") (pin "12") (pinfunction "DCD#_12") (pintype "passive"))
    )
    (net (code "83") (name "unconnected-(U6-DSR#-Pad10)") (class "Default")
      (node (ref "U6") (pin "10") (pinfunction "DSR#_10") (pintype "passive"))
    )
    (net (code "84") (name "unconnected-(U6-R232-Pad15)") (class "Default")
      (node (ref "U6") (pin "15") (pinfunction "R232_15") (pintype "passive"))
    )
    (net (code "85") (name "unconnected-(U6-RI#-Pad11)") (class "Default")
      (node (ref "U6") (pin "11") (pinfunction "RI#_11") (pintype "passive"))
    )
    (net (code "86") (name "unconnected-(U7-Vref-Pad5)") (class "Default")
      (node (ref "U7") (pin "5") (pinfunction "Vref_5") (pintype "output"))
    )
  )
)
